# SERVO.net
KiCad netlist of a schematic drawn in Altium Designer
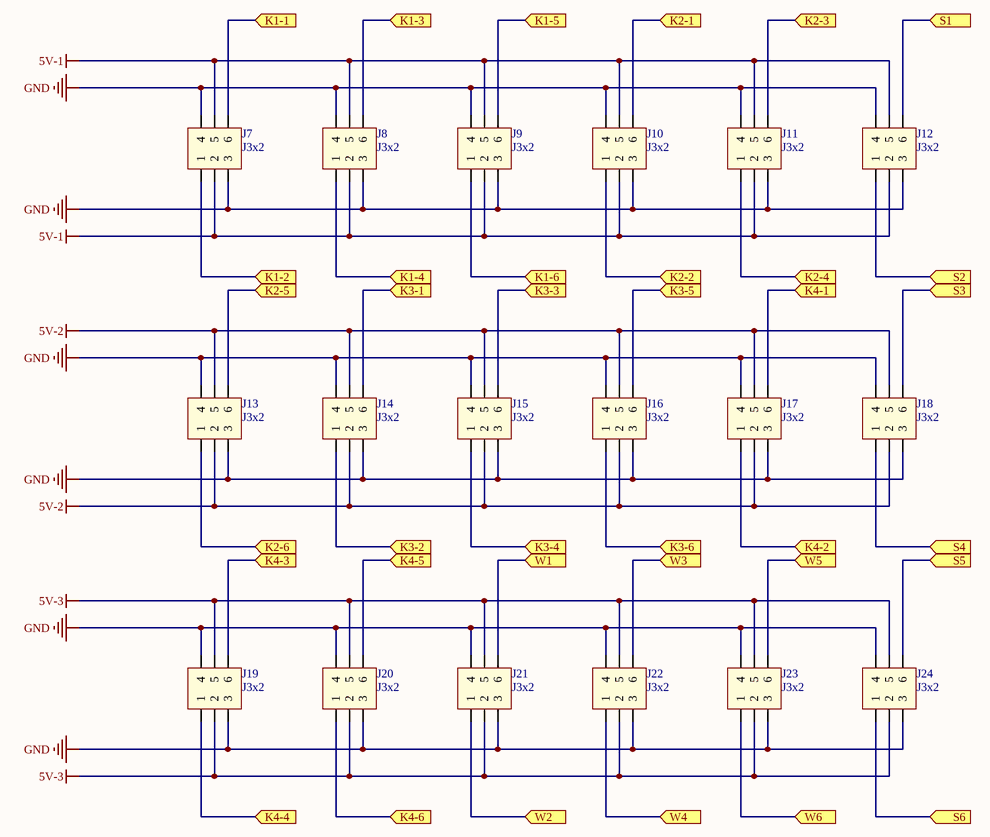
[diagram p0: SERVO.SchDoc]

(export (version "E")
  (design (tool "Eeschema 10.0.6"))
  (components
    (comp (ref "J7")
      (value "J3x2")
      (footprint "J3-D2T")
      (description "Connector 3x2")
      (libsource (lib "My Library") (part "JP3x2"))
    )
    (comp (ref "J8")
      (value "J3x2")
      (footprint "J3-D2T")
      (description "Connector 3x2")
      (libsource (lib "My Library") (part "JP3x2"))
    )
    (comp (ref "J9")
      (value "J3x2")
      (footprint "J3-D2T")
      (description "Connector 3x2")
      (libsource (lib "My Library") (part "JP3x2"))
    )
    (comp (ref "J10")
      (value "J3x2")
      (footprint "J3-D2T")
      (description "Connector 3x2")
      (libsource (lib "My Library") (part "JP3x2"))
    )
    (comp (ref "J11")
      (value "J3x2")
      (footprint "J3-D2T")
      (description "Connector 3x2")
      (libsource (lib "My Library") (part "JP3x2"))
    )
    (comp (ref "J12")
      (value "J3x2")
      (footprint "J3-D2T")
      (description "Connector 3x2")
      (libsource (lib "My Library") (part "JP3x2"))
    )
    (comp (ref "J13")
      (value "J3x2")
      (footprint "J3-D2T")
      (description "Connector 3x2")
      (libsource (lib "My Library") (part "JP3x2"))
    )
    (comp (ref "J14")
      (value "J3x2")
      (footprint "J3-D2T")
      (description "Connector 3x2")
      (libsource (lib "My Library") (part "JP3x2"))
    )
    (comp (ref "J15")
      (value "J3x2")
      (footprint "J3-D2T")
      (description "Connector 3x2")
      (libsource (lib "My Library") (part "JP3x2"))
    )
    (comp (ref "J16")
      (value "J3x2")
      (footprint "J3-D2T")
      (description "Connector 3x2")
      (libsource (lib "My Library") (part "JP3x2"))
    )
    (comp (ref "J17")
      (value "J3x2")
      (footprint "J3-D2T")
      (description "Connector 3x2")
      (libsource (lib "My Library") (part "JP3x2"))
    )
    (comp (ref "J18")
      (value "J3x2")
      (footprint "J3-D2T")
      (description "Connector 3x2")
      (libsource (lib "My Library") (part "JP3x2"))
    )
    (comp (ref "J19")
      (value "J3x2")
      (footprint "J3-D2T")
      (description "Connector 3x2")
      (libsource (lib "My Library") (part "JP3x2"))
    )
    (comp (ref "J20")
      (value "J3x2")
      (footprint "J3-D2T")
      (description "Connector 3x2")
      (libsource (lib "My Library") (part "JP3x2"))
    )
    (comp (ref "J21")
      (value "J3x2")
      (footprint "J3-D2T")
      (description "Connector 3x2")
      (libsource (lib "My Library") (part "JP3x2"))
    )
    (comp (ref "J22")
      (value "J3x2")
      (footprint "J3-D2T")
      (description "Connector 3x2")
      (libsource (lib "My Library") (part "JP3x2"))
    )
    (comp (ref "J23")
      (value "J3x2")
      (footprint "J3-D2T")
      (description "Connector 3x2")
      (libsource (lib "My Library") (part "JP3x2"))
    )
    (comp (ref "J24")
      (value "J3x2")
      (footprint "J3-D2T")
      (description "Connector 3x2")
      (libsource (lib "My Library") (part "JP3x2"))
    )
  )
  (nets
    (net (code "1") (name "/K1-1") (class "Default")
      (node (ref "J7") (pin "6") (pinfunction "6_6") (pintype "passive"))
    )
    (net (code "2") (name "/K1-2") (class "Default")
      (node (ref "J7") (pin "1") (pinfunction "1_1") (pintype "passive"))
    )
    (net (code "3") (name "/K1-3") (class "Default")
      (node (ref "J8") (pin "6") (pinfunction "6_6") (pintype "passive"))
    )
    (net (code "4") (name "/K1-4") (class "Default")
      (node (ref "J8") (pin "1") (pinfunction "1_1") (pintype "passive"))
    )
    (net (code "5") (name "/K1-5") (class "Default")
      (node (ref "J9") (pin "6") (pinfunction "6_6") (pintype "passive"))
    )
    (net (code "6") (name "/K1-6") (class "Default")
      (node (ref "J9") (pin "1") (pinfunction "1_1") (pintype "passive"))
    )
    (net (code "7") (name "/K2-1") (class "Default")
      (node (ref "J10") (pin "6") (pinfunction "6_6") (pintype "passive"))
    )
    (net (code "8") (name "/K2-2") (class "Default")
      (node (ref "J10") (pin "1") (pinfunction "1_1") (pintype "passive"))
    )
    (net (code "9") (name "/K2-3") (class "Default")
      (node (ref "J11") (pin "6") (pinfunction "6_6") (pintype "passive"))
    )
    (net (code "10") (name "/K2-4") (class "Default")
      (node (ref "J11") (pin "1") (pinfunction "1_1") (pintype "passive"))
    )
    (net (code "11") (name "/K2-5") (class "Default")
      (node (ref "J13") (pin "6") (pinfunction "6_6") (pintype "passive"))
    )
    (net (code "12") (name "/K2-6") (class "Default")
      (node (ref "J13") (pin "1") (pinfunction "1_1") (pintype "passive"))
    )
    (net (code "13") (name "/K3-1") (class "Default")
      (node (ref "J14") (pin "6") (pinfunction "6_6") (pintype "passive"))
    )
    (net (code "14") (name "/K3-2") (class "Default")
      (node (ref "J14") (pin "1") (pinfunction "1_1") (pintype "passive"))
    )
    (net (code "15") (name "/K3-3") (class "Default")
      (node (ref "J15") (pin "6") (pinfunction "6_6") (pintype "passive"))
    )
    (net (code "16") (name "/K3-4") (class "Default")
      (node (ref "J15") (pin "1") (pinfunction "1_1") (pintype "passive"))
    )
    (net (code "17") (name "/K3-5") (class "Default")
      (node (ref "J16") (pin "6") (pinfunction "6_6") (pintype "passive"))
    )
    (net (code "18") (name "/K3-6") (class "Default")
      (node (ref "J16") (pin "1") (pinfunction "1_1") (pintype "passive"))
    )
    (net (code "19") (name "/K4-1") (class "Default")
      (node (ref "J17") (pin "6") (pinfunction "6_6") (pintype "passive"))
    )
    (net (code "20") (name "/K4-2") (class "Default")
      (node (ref "J17") (pin "1") (pinfunction "1_1") (pintype "passive"))
    )
    (net (code "21") (name "/K4-3") (class "Default")
      (node (ref "J19") (pin "6") (pinfunction "6_6") (pintype "passive"))
    )
    (net (code "22") (name "/K4-4") (class "Default")
      (node (ref "J19") (pin "1") (pinfunction "1_1") (pintype "passive"))
    )
    (net (code "23") (name "/K4-5") (class "Default")
      (node (ref "J20") (pin "6") (pinfunction "6_6") (pintype "passive"))
    )
    (net (code "24") (name "/K4-6") (class "Default")
      (node (ref "J20") (pin "1") (pinfunction "1_1") (pintype "passive"))
    )
    (net (code "25") (name "/S1") (class "Default")
      (node (ref "J12") (pin "6") (pinfunction "6_6") (pintype "passive"))
    )
    (net (code "26") (name "/S2") (class "Default")
      (node (ref "J12") (pin "1") (pinfunction "1_1") (pintype "passive"))
    )
    (net (code "27") (name "/S3") (class "Default")
      (node (ref "J18") (pin "6") (pinfunction "6_6") (pintype "passive"))
    )
    (net (code "28") (name "/S4") (class "Default")
      (node (ref "J18") (pin "1") (pinfunction "1_1") (pintype "passive"))
    )
    (net (code "29") (name "/S5") (class "Default")
      (node (ref "J24") (pin "6") (pinfunction "6_6") (pintype "passive"))
    )
    (net (code "30") (name "/S6") (class "Default")
      (node (ref "J24") (pin "1") (pinfunction "1_1") (pintype "passive"))
    )
    (net (code "31") (name "/W1") (class "Default")
      (node (ref "J21") (pin "6") (pinfunction "6_6") (pintype "passive"))
    )
    (net (code "32") (name "/W2") (class "Default")
      (node (ref "J21") (pin "1") (pinfunction "1_1") (pintype "passive"))
    )
    (net (code "33") (name "/W3") (class "Default")
      (node (ref "J22") (pin "6") (pinfunction "6_6") (pintype "passive"))
    )
    (net (code "34") (name "/W4") (class "Default")
      (node (ref "J22") (pin "1") (pinfunction "1_1") (pintype "passive"))
    )
    (net (code "35") (name "/W5") (class "Default")
      (node (ref "J23") (pin "6") (pinfunction "6_6") (pintype "passive"))
    )
    (net (code "36") (name "/W6") (class "Default")
      (node (ref "J23") (pin "1") (pinfunction "1_1") (pintype "passive"))
    )
    (net (code "37") (name "5V-1") (class "Default")
      (node (ref "J10") (pin "2") (pinfunction "2_2") (pintype "passive"))
      (node (ref "J10") (pin "5") (pinfunction "5_5") (pintype "passive"))
      (node (ref "J11") (pin "2") (pinfunction "2_2") (pintype "passive"))
      (node (ref "J11") (pin "5") (pinfunction "5_5") (pintype "passive"))
      (node (ref "J12") (pin "2") (pinfunction "2_2") (pintype "passive"))
      (node (ref "J12") (pin "5") (pinfunction "5_5") (pintype "passive"))
      (node (ref "J7") (pin "2") (pinfunction "2_2") (pintype "passive"))
      (node (ref "J7") (pin "5") (pinfunction "5_5") (pintype "passive"))
      (node (ref "J8") (pin "2") (pinfunction "2_2") (pintype "passive"))
      (node (ref "J8") (pin "5") (pinfunction "5_5") (pintype "passive"))
      (node (ref "J9") (pin "2") (pinfunction "2_2") (pintype "passive"))
      (node (ref "J9") (pin "5") (pinfunction "5_5") (pintype "passive"))
    )
    (net (code "38") (name "5V-2") (class "Default")
      (node (ref "J13") (pin "2") (pinfunction "2_2") (pintype "passive"))
      (node (ref "J13") (pin "5") (pinfunction "5_5") (pintype "passive"))
      (node (ref "J14") (pin "2") (pinfunction "2_2") (pintype "passive"))
      (node (ref "J14") (pin "5") (pinfunction "5_5") (pintype "passive"))
      (node (ref "J15") (pin "2") (pinfunction "2_2") (pintype "passive"))
      (node (ref "J15") (pin "5") (pinfunction "5_5") (pintype "passive"))
      (node (ref "J16") (pin "2") (pinfunction "2_2") (pintype "passive"))
      (node (ref "J16") (pin "5") (pinfunction "5_5") (pintype "passive"))
      (node (ref "J17") (pin "2") (pinfunction "2_2") (pintype "passive"))
      (node (ref "J17") (pin "5") (pinfunction "5_5") (pintype "passive"))
      (node (ref "J18") (pin "2") (pinfunction "2_2") (pintype "passive"))
      (node (ref "J18") (pin "5") (pinfunction "5_5") (pintype "passive"))
    )
    (net (code "39") (name "5V-3") (class "Default")
      (node (ref "J19") (pin "2") (pinfunction "2_2") (pintype "passive"))
      (node (ref "J19") (pin "5") (pinfunction "5_5") (pintype "passive"))
      (node (ref "J20") (pin "2") (pinfunction "2_2") (pintype "passive"))
      (node (ref "J20") (pin "5") (pinfunction "5_5") (pintype "passive"))
      (node (ref "J21") (pin "2") (pinfunction "2_2") (pintype "passive"))
      (node (ref "J21") (pin "5") (pinfunction "5_5") (pintype "passive"))
      (node (ref "J22") (pin "2") (pinfunction "2_2") (pintype "passive"))
      (node (ref "J22") (pin "5") (pinfunction "5_5") (pintype "passive"))
      (node (ref "J23") (pin "2") (pinfunction "2_2") (pintype "passive"))
      (node (ref "J23") (pin "5") (pinfunction "5_5") (pintype "passive"))
      (node (ref "J24") (pin "2") (pinfunction "2_2") (pintype "passive"))
      (node (ref "J24") (pin "5") (pinfunction "5_5") (pintype "passive"))
    )
    (net (code "40") (name "GND") (class "Default")
      (node (ref "J10") (pin "3") (pinfunction "3_3") (pintype "passive"))
      (node (ref "J10") (pin "4") (pinfunction "4_4") (pintype "passive"))
      (node (ref "J11") (pin "3") (pinfunction "3_3") (pintype "passive"))
      (node (ref "J11") (pin "4") (pinfunction "4_4") (pintype "passive"))
      (node (ref "J12") (pin "3") (pinfunction "3_3") (pintype "passive"))
      (node (ref "J12") (pin "4") (pinfunction "4_4") (pintype "passive"))
      (node (ref "J13") (pin "3") (pinfunction "3_3") (pintype "passive"))
      (node (ref "J13") (pin "4") (pinfunction "4_4") (pintype "passive"))
      (node (ref "J14") (pin "3") (pinfunction "3_3") (pintype "passive"))
      (node (ref "J14") (pin "4") (pinfunction "4_4") (pintype "passive"))
      (node (ref "J15") (pin "3") (pinfunction "3_3") (pintype "passive"))
      (node (ref "J15") (pin "4") (pinfunction "4_4") (pintype "passive"))
      (node (ref "J16") (pin "3") (pinfunction "3_3") (pintype "passive"))
      (node (ref "J16") (pin "4") (pinfunction "4_4") (pintype "passive"))
      (node (ref "J17") (pin "3") (pinfunction "3_3") (pintype "passive"))
      (node (ref "J17") (pin "4") (pinfunction "4_4") (pintype "passive"))
      (node (ref "J18") (pin "3") (pinfunction "3_3") (pintype "passive"))
      (node (ref "J18") (pin "4") (pinfunction "4_4") (pintype "passive"))
      (node (ref "J19") (pin "3") (pinfunction "3_3") (pintype "passive"))
      (node (ref "J19") (pin "4") (pinfunction "4_4") (pintype "passive"))
      (node (ref "J20") (pin "3") (pinfunction "3_3") (pintype "passive"))
      (node (ref "J20") (pin "4") (pinfunction "4_4") (pintype "passive"))
      (node (ref "J21") (pin "3") (pinfunction "3_3") (pintype "passive"))
      (node (ref "J21") (pin "4") (pinfunction "4_4") (pintype "passive"))
      (node (ref "J22") (pin "3") (pinfunction "3_3") (pintype "passive"))
      (node (ref "J22") (pin "4") (pinfunction "4_4") (pintype "passive"))
      (node (ref "J23") (pin "3") (pinfunction "3_3") (pintype "passive"))
      (node (ref "J23") (pin "4") (pinfunction "4_4") (pintype "passive"))
      (node (ref "J24") (pin "3") (pinfunction "3_3") (pintype "passive"))
      (node (ref "J24") (pin "4") (pinfunction "4_4") (pintype "passive"))
      (node (ref "J7") (pin "3") (pinfunction "3_3") (pintype "passive"))
      (node (ref "J7") (pin "4") (pinfunction "4_4") (pintype "passive"))
      (node (ref "J8") (pin "3") (pinfunction "3_3") (pintype "passive"))
      (node (ref "J8") (pin "4") (pinfunction "4_4") (pintype "passive"))
      (node (ref "J9") (pin "3") (pinfunction "3_3") (pintype "passive"))
      (node (ref "J9") (pin "4") (pinfunction "4_4") (pintype "passive"))
    )
  )
)
